# Mixer-Analog-OPA1644-Rev-E_TH_remaining0.net
KiCad netlist of a schematic drawn in EAGLE
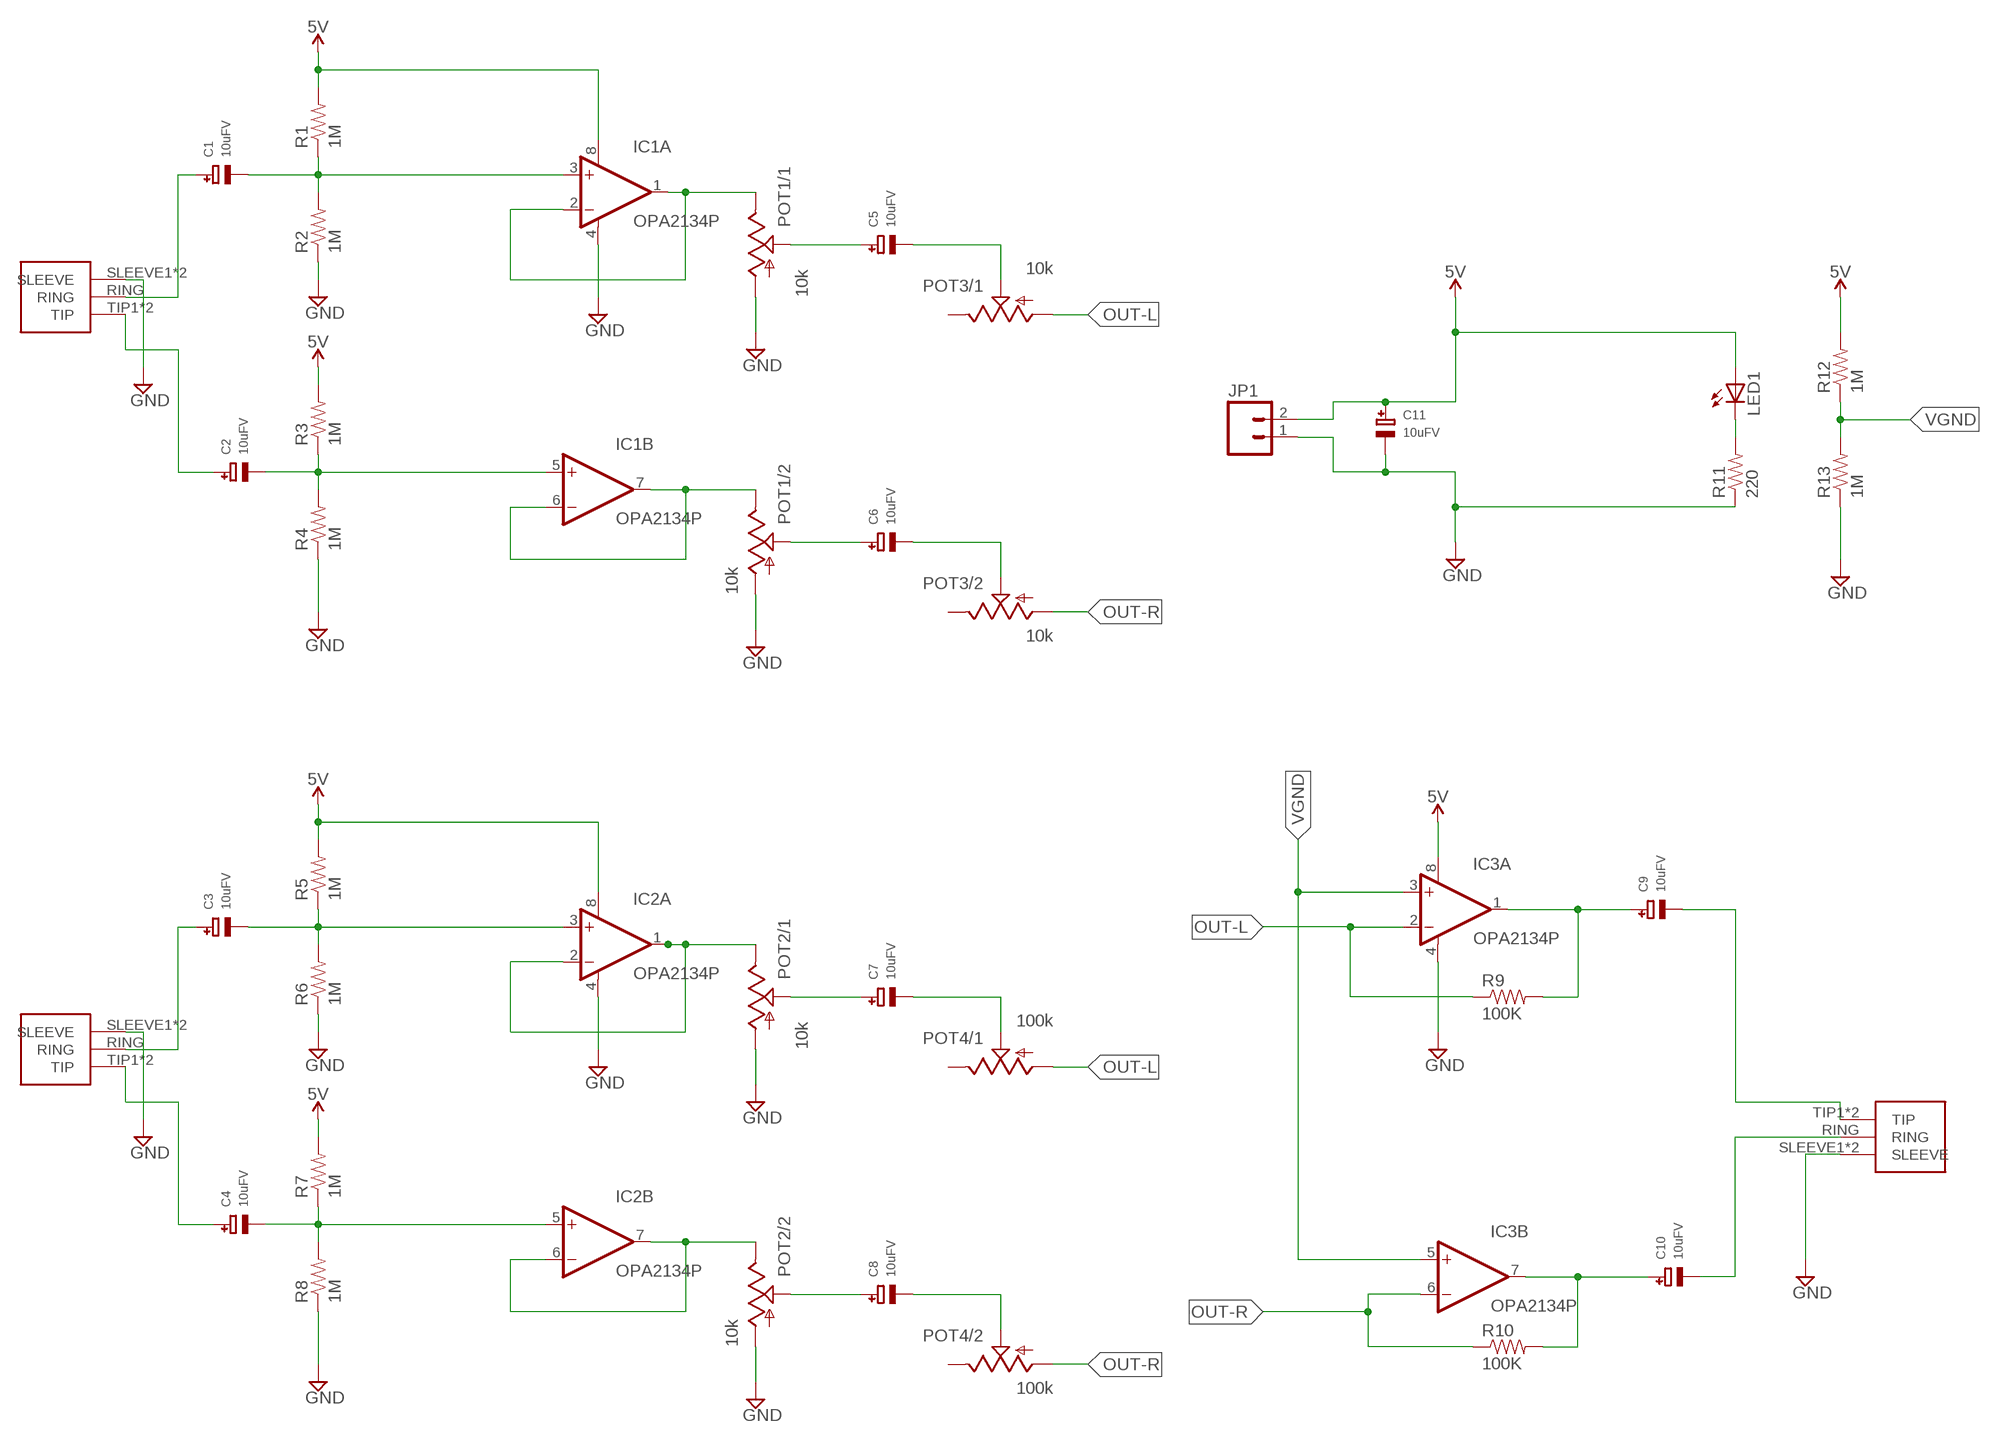
[diagram p0: schematic, sheet 1]

(export (version "E")
  (design (tool "Eeschema 10.0.6"))
  (components
    (comp (ref "C1")
      (value "10uFV")
      (footprint "eagle-import:CELEC_3.5MM_8MM")
      (libsource (lib "eagle-import") (part "CAP_ELECTROLYTICPTH_3.5MMGRID_8MMDIA"))
    )
    (comp (ref "C2")
      (value "10uFV")
      (footprint "eagle-import:CELEC_3.5MM_8MM")
      (libsource (lib "eagle-import") (part "CAP_ELECTROLYTICPTH_3.5MMGRID_8MMDIA"))
    )
    (comp (ref "C3")
      (value "10uFV")
      (footprint "eagle-import:CELEC_3.5MM_8MM")
      (libsource (lib "eagle-import") (part "CAP_ELECTROLYTICPTH_3.5MMGRID_8MMDIA"))
    )
    (comp (ref "C4")
      (value "10uFV")
      (footprint "eagle-import:CELEC_3.5MM_8MM")
      (libsource (lib "eagle-import") (part "CAP_ELECTROLYTICPTH_3.5MMGRID_8MMDIA"))
    )
    (comp (ref "C5")
      (value "10uFV")
      (footprint "eagle-import:CELEC_3.5MM_8MM")
      (libsource (lib "eagle-import") (part "CAP_ELECTROLYTICPTH_3.5MMGRID_8MMDIA"))
    )
    (comp (ref "C6")
      (value "10uFV")
      (footprint "eagle-import:CELEC_3.5MM_8MM")
      (libsource (lib "eagle-import") (part "CAP_ELECTROLYTICPTH_3.5MMGRID_8MMDIA"))
    )
    (comp (ref "C7")
      (value "10uFV")
      (footprint "eagle-import:CELEC_3.5MM_8MM")
      (libsource (lib "eagle-import") (part "CAP_ELECTROLYTICPTH_3.5MMGRID_8MMDIA"))
    )
    (comp (ref "C8")
      (value "10uFV")
      (footprint "eagle-import:CELEC_3.5MM_8MM")
      (libsource (lib "eagle-import") (part "CAP_ELECTROLYTICPTH_3.5MMGRID_8MMDIA"))
    )
    (comp (ref "C9")
      (value "10uFV")
      (footprint "eagle-import:CELEC_3.5MM_8MM")
      (libsource (lib "eagle-import") (part "CAP_ELECTROLYTICPTH_3.5MMGRID_8MMDIA"))
    )
    (comp (ref "C10")
      (value "10uFV")
      (footprint "eagle-import:CELEC_3.5MM_8MM")
      (libsource (lib "eagle-import") (part "CAP_ELECTROLYTICPTH_3.5MMGRID_8MMDIA"))
    )
    (comp (ref "C11")
      (value "10uFV")
      (footprint "eagle-import:CELEC_3.5MM_8MM")
      (libsource (lib "eagle-import") (part "CAP_ELECTROLYTICPTH_3.5MMGRID_8MMDIA"))
    )
    (comp (ref "IC1")
      (value "OPA2134P")
      (footprint "eagle-import:DIL08")
      (fields (field (name "MF") "TEXAS INSTRUMENTS") (field (name "MPN") "OPA2134PA"))
      (libsource (lib "eagle-import") (part "OPA2134P"))
    )
    (comp (ref "IC2")
      (value "OPA2134P")
      (footprint "eagle-import:DIL08")
      (fields (field (name "MF") "TEXAS INSTRUMENTS") (field (name "MPN") "OPA2134PA"))
      (libsource (lib "eagle-import") (part "OPA2134P"))
    )
    (comp (ref "IC3")
      (value "OPA2134P")
      (footprint "eagle-import:DIL08")
      (fields (field (name "MF") "TEXAS INSTRUMENTS") (field (name "MPN") "OPA2134PA"))
      (libsource (lib "eagle-import") (part "OPA2134P"))
    )
    (comp (ref "J1")
      (value "1/8\"-F-STEREO-PCB")
      (footprint "eagle-import:1_8_-F-STEREO-PCB")
      (libsource (lib "eagle-import") (part "1/8{dblquote}-F-STEREO-PCB"))
    )
    (comp (ref "J2")
      (value "1/8\"-F-STEREO-PCB")
      (footprint "eagle-import:1_8_-F-STEREO-PCB")
      (libsource (lib "eagle-import") (part "1/8{dblquote}-F-STEREO-PCB"))
    )
    (comp (ref "J3")
      (value "1/8\"-F-STEREO-PCB")
      (footprint "eagle-import:1_8_-F-STEREO-PCB")
      (libsource (lib "eagle-import") (part "1/8{dblquote}-F-STEREO-PCB"))
    )
    (comp (ref "JP1")
      (value "M02LOCK")
      (footprint "eagle-import:1X02_LOCK")
      (libsource (lib "eagle-import") (part "M02LOCK"))
    )
    (comp (ref "LED1")
      (value "LED3MM")
      (footprint "eagle-import:LED3MM")
      (libsource (lib "eagle-import") (part "LED3MM"))
    )
    (comp (ref "POT1")
      (value "10k")
      (footprint "eagle-import:PTV112")
      (fields
        (field (name "MF") "STMicroelectronics")
        (field (name "MP") "PTV112")
        (field (name "SPICEPREFIX") "J")
      )
      (libsource (lib "eagle-import") (part "POT-DUAL-PTV112-4420"))
    )
    (comp (ref "POT2")
      (value "10k")
      (footprint "eagle-import:PTV112")
      (fields
        (field (name "MF") "STMicroelectronics")
        (field (name "MP") "PTV112")
        (field (name "SPICEPREFIX") "J")
      )
      (libsource (lib "eagle-import") (part "POT-DUAL-PTV112-4420"))
    )
    (comp (ref "POT3")
      (value "10k")
      (footprint "eagle-import:PTV112")
      (fields
        (field (name "MF") "STMicroelectronics")
        (field (name "MP") "PTV112")
        (field (name "SPICEPREFIX") "J")
      )
      (libsource (lib "eagle-import") (part "POT-DUAL-PTV112-4420"))
    )
    (comp (ref "POT4")
      (value "100k")
      (footprint "eagle-import:PTV112")
      (fields
        (field (name "MF") "STMicroelectronics")
        (field (name "MP") "PTV112")
        (field (name "SPICEPREFIX") "J")
      )
      (libsource (lib "eagle-import") (part "POT-DUAL-PTV112-4420"))
    )
    (comp (ref "R1")
      (value "1M")
      (footprint "eagle-import:AXIAL-0.3EZ")
      (fields (field (name "SPICEPREFIX") "R"))
      (libsource (lib "eagle-import") (part "RESISTOREZ"))
    )
    (comp (ref "R2")
      (value "1M")
      (footprint "eagle-import:AXIAL-0.3")
      (fields (field (name "SPICEPREFIX") "R"))
      (libsource (lib "eagle-import") (part "RESISTORAXIAL-0.3"))
    )
    (comp (ref "R3")
      (value "1M")
      (footprint "eagle-import:AXIAL-0.3EZ")
      (fields (field (name "SPICEPREFIX") "R"))
      (libsource (lib "eagle-import") (part "RESISTOREZ"))
    )
    (comp (ref "R4")
      (value "1M")
      (footprint "eagle-import:AXIAL-0.3EZ")
      (fields (field (name "SPICEPREFIX") "R"))
      (libsource (lib "eagle-import") (part "RESISTOREZ"))
    )
    (comp (ref "R5")
      (value "1M")
      (footprint "eagle-import:AXIAL-0.3EZ")
      (fields (field (name "SPICEPREFIX") "R"))
      (libsource (lib "eagle-import") (part "RESISTOREZ"))
    )
    (comp (ref "R6")
      (value "1M")
      (footprint "eagle-import:AXIAL-0.3EZ")
      (fields (field (name "SPICEPREFIX") "R"))
      (libsource (lib "eagle-import") (part "RESISTOREZ"))
    )
    (comp (ref "R7")
      (value "1M")
      (footprint "eagle-import:AXIAL-0.3EZ")
      (fields (field (name "SPICEPREFIX") "R"))
      (libsource (lib "eagle-import") (part "RESISTOREZ"))
    )
    (comp (ref "R8")
      (value "1M")
      (footprint "eagle-import:AXIAL-0.3EZ")
      (fields (field (name "SPICEPREFIX") "R"))
      (libsource (lib "eagle-import") (part "RESISTOREZ"))
    )
    (comp (ref "R9")
      (value "100K")
      (footprint "eagle-import:AXIAL-0.3EZ")
      (fields (field (name "SPICEPREFIX") "R"))
      (libsource (lib "eagle-import") (part "RESISTOREZ"))
    )
    (comp (ref "R10")
      (value "100K")
      (footprint "eagle-import:AXIAL-0.3EZ")
      (fields (field (name "SPICEPREFIX") "R"))
      (libsource (lib "eagle-import") (part "RESISTOREZ"))
    )
    (comp (ref "R11")
      (value "220")
      (footprint "eagle-import:AXIAL-0.3EZ")
      (libsource (lib "eagle-import") (part "RESISTOREZ"))
    )
    (comp (ref "R12")
      (value "1M")
      (footprint "eagle-import:AXIAL-0.3EZ")
      (libsource (lib "eagle-import") (part "RESISTOREZ"))
    )
    (comp (ref "R13")
      (value "1M")
      (footprint "eagle-import:AXIAL-0.3EZ")
      (libsource (lib "eagle-import") (part "RESISTOREZ"))
    )
  )
  (nets
    (net (code "1") (name "5V") (class "Default")
      (node (ref "C11") (pin "+") (pinfunction "+_+") (pintype "passive"))
      (node (ref "IC1") (pin "8") (pinfunction "V+_8") (pintype "power_in"))
      (node (ref "IC2") (pin "8") (pinfunction "V+_8") (pintype "power_in"))
      (node (ref "IC3") (pin "8") (pinfunction "V+_8") (pintype "power_in"))
      (node (ref "JP1") (pin "2") (pinfunction "2_2") (pintype "passive"))
      (node (ref "LED1") (pin "A") (pinfunction "A_A") (pintype "passive"))
      (node (ref "R1") (pin "P$2") (pinfunction "2_P$2") (pintype "passive"))
      (node (ref "R12") (pin "P$2") (pinfunction "2_P$2") (pintype "passive"))
      (node (ref "R3") (pin "P$2") (pinfunction "2_P$2") (pintype "passive"))
      (node (ref "R5") (pin "P$2") (pinfunction "2_P$2") (pintype "passive"))
      (node (ref "R7") (pin "P$2") (pinfunction "2_P$2") (pintype "passive"))
    )
    (net (code "2") (name "GND") (class "Default")
      (node (ref "C11") (pin "-") (pinfunction "-_-") (pintype "passive"))
      (node (ref "IC1") (pin "4") (pinfunction "V-_4") (pintype "power_in"))
      (node (ref "IC2") (pin "4") (pinfunction "V-_4") (pintype "power_in"))
      (node (ref "IC3") (pin "4") (pinfunction "V-_4") (pintype "power_in"))
      (node (ref "J1") (pin "SLEEVE1") (pinfunction "SLEEVE_SLEEVE1") (pintype "bidirectional"))
      (node (ref "J1") (pin "SLEEVE2") (pinfunction "SLEEVE_SLEEVE2") (pintype "bidirectional"))
      (node (ref "J2") (pin "SLEEVE1") (pinfunction "SLEEVE_SLEEVE1") (pintype "bidirectional"))
      (node (ref "J2") (pin "SLEEVE2") (pinfunction "SLEEVE_SLEEVE2") (pintype "bidirectional"))
      (node (ref "J3") (pin "SLEEVE1") (pinfunction "SLEEVE_SLEEVE1") (pintype "bidirectional"))
      (node (ref "J3") (pin "SLEEVE2") (pinfunction "SLEEVE_SLEEVE2") (pintype "bidirectional"))
      (node (ref "JP1") (pin "1") (pinfunction "1_1") (pintype "passive"))
      (node (ref "POT1") (pin "1.1") (pinfunction "A_1.1") (pintype "passive"))
      (node (ref "POT1") (pin "2.1") (pinfunction "A_2.1") (pintype "passive"))
      (node (ref "POT2") (pin "1.1") (pinfunction "A_1.1") (pintype "passive"))
      (node (ref "POT2") (pin "2.1") (pinfunction "A_2.1") (pintype "passive"))
      (node (ref "R11") (pin "P$1") (pinfunction "1_P$1") (pintype "passive"))
      (node (ref "R13") (pin "P$1") (pinfunction "1_P$1") (pintype "passive"))
      (node (ref "R2") (pin "P$1") (pinfunction "1_P$1") (pintype "passive"))
      (node (ref "R4") (pin "P$1") (pinfunction "1_P$1") (pintype "passive"))
      (node (ref "R6") (pin "P$1") (pinfunction "1_P$1") (pintype "passive"))
      (node (ref "R8") (pin "P$1") (pinfunction "1_P$1") (pintype "passive"))
    )
    (net (code "3") (name "Net-(C1-Pad+)") (class "Default")
      (node (ref "C1") (pin "+") (pinfunction "+_+") (pintype "passive"))
      (node (ref "J1") (pin "RING") (pinfunction "RING_RING") (pintype "bidirectional"))
    )
    (net (code "4") (name "Net-(C2-Pad+)") (class "Default")
      (node (ref "C2") (pin "+") (pinfunction "+_+") (pintype "passive"))
      (node (ref "J1") (pin "TIP1") (pinfunction "TIP_TIP1") (pintype "bidirectional"))
      (node (ref "J1") (pin "TIP2") (pinfunction "TIP_TIP2") (pintype "bidirectional"))
    )
    (net (code "5") (name "Net-(C3-Pad+)") (class "Default")
      (node (ref "C3") (pin "+") (pinfunction "+_+") (pintype "passive"))
      (node (ref "J2") (pin "RING") (pinfunction "RING_RING") (pintype "bidirectional"))
    )
    (net (code "6") (name "Net-(C4-Pad+)") (class "Default")
      (node (ref "C4") (pin "+") (pinfunction "+_+") (pintype "passive"))
      (node (ref "J2") (pin "TIP1") (pinfunction "TIP_TIP1") (pintype "bidirectional"))
      (node (ref "J2") (pin "TIP2") (pinfunction "TIP_TIP2") (pintype "bidirectional"))
    )
    (net (code "7") (name "Net-(C9-Pad-)") (class "Default")
      (node (ref "C9") (pin "-") (pinfunction "-_-") (pintype "passive"))
      (node (ref "J3") (pin "TIP1") (pinfunction "TIP_TIP1") (pintype "bidirectional"))
      (node (ref "J3") (pin "TIP2") (pinfunction "TIP_TIP2") (pintype "bidirectional"))
    )
    (net (code "8") (name "Net-(C10-Pad-)") (class "Default")
      (node (ref "C10") (pin "-") (pinfunction "-_-") (pintype "passive"))
      (node (ref "J3") (pin "RING") (pinfunction "RING_RING") (pintype "bidirectional"))
    )
    (net (code "9") (name "Net-(IC1A-+IN)") (class "Default")
      (node (ref "C1") (pin "-") (pinfunction "-_-") (pintype "passive"))
      (node (ref "IC1") (pin "3") (pinfunction "+IN_3") (pintype "input"))
      (node (ref "R1") (pin "P$1") (pinfunction "1_P$1") (pintype "passive"))
      (node (ref "R2") (pin "P$2") (pinfunction "2_P$2") (pintype "passive"))
    )
    (net (code "10") (name "Net-(IC1A--IN)") (class "Default")
      (node (ref "IC1") (pin "1") (pinfunction "OUT_1") (pintype "output"))
      (node (ref "IC1") (pin "2") (pinfunction "-IN_2") (pintype "input"))
      (node (ref "POT1") (pin "1.3") (pinfunction "E_1.3") (pintype "passive"))
    )
    (net (code "11") (name "Net-(IC1B-+IN)") (class "Default")
      (node (ref "C2") (pin "-") (pinfunction "-_-") (pintype "passive"))
      (node (ref "IC1") (pin "5") (pinfunction "+IN_5") (pintype "input"))
      (node (ref "R3") (pin "P$1") (pinfunction "1_P$1") (pintype "passive"))
      (node (ref "R4") (pin "P$2") (pinfunction "2_P$2") (pintype "passive"))
    )
    (net (code "12") (name "Net-(IC1B--IN)") (class "Default")
      (node (ref "IC1") (pin "6") (pinfunction "-IN_6") (pintype "input"))
      (node (ref "IC1") (pin "7") (pinfunction "OUT_7") (pintype "output"))
      (node (ref "POT1") (pin "2.3") (pinfunction "E_2.3") (pintype "passive"))
    )
    (net (code "13") (name "Net-(IC2A-+IN)") (class "Default")
      (node (ref "C3") (pin "-") (pinfunction "-_-") (pintype "passive"))
      (node (ref "IC2") (pin "3") (pinfunction "+IN_3") (pintype "input"))
      (node (ref "R5") (pin "P$1") (pinfunction "1_P$1") (pintype "passive"))
      (node (ref "R6") (pin "P$2") (pinfunction "2_P$2") (pintype "passive"))
    )
    (net (code "14") (name "Net-(IC2A--IN)") (class "Default")
      (node (ref "IC2") (pin "1") (pinfunction "OUT_1") (pintype "output"))
      (node (ref "IC2") (pin "2") (pinfunction "-IN_2") (pintype "input"))
      (node (ref "POT2") (pin "1.3") (pinfunction "E_1.3") (pintype "passive"))
    )
    (net (code "15") (name "Net-(IC2B-+IN)") (class "Default")
      (node (ref "C4") (pin "-") (pinfunction "-_-") (pintype "passive"))
      (node (ref "IC2") (pin "5") (pinfunction "+IN_5") (pintype "input"))
      (node (ref "R7") (pin "P$1") (pinfunction "1_P$1") (pintype "passive"))
      (node (ref "R8") (pin "P$2") (pinfunction "2_P$2") (pintype "passive"))
    )
    (net (code "16") (name "Net-(IC2B--IN)") (class "Default")
      (node (ref "IC2") (pin "6") (pinfunction "-IN_6") (pintype "input"))
      (node (ref "IC2") (pin "7") (pinfunction "OUT_7") (pintype "output"))
      (node (ref "POT2") (pin "2.3") (pinfunction "E_2.3") (pintype "passive"))
    )
    (net (code "17") (name "Net-(IC3A-OUT)") (class "Default")
      (node (ref "C9") (pin "+") (pinfunction "+_+") (pintype "passive"))
      (node (ref "IC3") (pin "1") (pinfunction "OUT_1") (pintype "output"))
      (node (ref "R9") (pin "P$2") (pinfunction "2_P$2") (pintype "passive"))
    )
    (net (code "18") (name "Net-(IC3B-OUT)") (class "Default")
      (node (ref "C10") (pin "+") (pinfunction "+_+") (pintype "passive"))
      (node (ref "IC3") (pin "7") (pinfunction "OUT_7") (pintype "output"))
      (node (ref "R10") (pin "P$2") (pinfunction "2_P$2") (pintype "passive"))
    )
    (net (code "19") (name "Net-(LED1-C)") (class "Default")
      (node (ref "LED1") (pin "K") (pinfunction "C_K") (pintype "passive"))
      (node (ref "R11") (pin "P$2") (pinfunction "2_P$2") (pintype "passive"))
    )
    (net (code "20") (name "Net-(POT1A-S)") (class "Default")
      (node (ref "C5") (pin "+") (pinfunction "+_+") (pintype "passive"))
      (node (ref "POT1") (pin "1.2") (pinfunction "S_1.2") (pintype "passive"))
    )
    (net (code "21") (name "Net-(POT1B-S)") (class "Default")
      (node (ref "C6") (pin "+") (pinfunction "+_+") (pintype "passive"))
      (node (ref "POT1") (pin "2.2") (pinfunction "S_2.2") (pintype "passive"))
    )
    (net (code "22") (name "Net-(POT2A-S)") (class "Default")
      (node (ref "C7") (pin "+") (pinfunction "+_+") (pintype "passive"))
      (node (ref "POT2") (pin "1.2") (pinfunction "S_1.2") (pintype "passive"))
    )
    (net (code "23") (name "Net-(POT2B-S)") (class "Default")
      (node (ref "C8") (pin "+") (pinfunction "+_+") (pintype "passive"))
      (node (ref "POT2") (pin "2.2") (pinfunction "S_2.2") (pintype "passive"))
    )
    (net (code "24") (name "Net-(POT3A-S)") (class "Default")
      (node (ref "C5") (pin "-") (pinfunction "-_-") (pintype "passive"))
      (node (ref "POT3") (pin "1.2") (pinfunction "S_1.2") (pintype "passive"))
    )
    (net (code "25") (name "Net-(POT3B-S)") (class "Default")
      (node (ref "C6") (pin "-") (pinfunction "-_-") (pintype "passive"))
      (node (ref "POT3") (pin "2.2") (pinfunction "S_2.2") (pintype "passive"))
    )
    (net (code "26") (name "Net-(POT4A-S)") (class "Default")
      (node (ref "C7") (pin "-") (pinfunction "-_-") (pintype "passive"))
      (node (ref "POT4") (pin "1.2") (pinfunction "S_1.2") (pintype "passive"))
    )
    (net (code "27") (name "Net-(POT4B-S)") (class "Default")
      (node (ref "C8") (pin "-") (pinfunction "-_-") (pintype "passive"))
      (node (ref "POT4") (pin "2.2") (pinfunction "S_2.2") (pintype "passive"))
    )
    (net (code "28") (name "OUT-L") (class "Default")
      (node (ref "IC3") (pin "2") (pinfunction "-IN_2") (pintype "input"))
      (node (ref "POT3") (pin "1.1") (pinfunction "A_1.1") (pintype "passive"))
      (node (ref "POT4") (pin "1.1") (pinfunction "A_1.1") (pintype "passive"))
      (node (ref "R9") (pin "P$1") (pinfunction "1_P$1") (pintype "passive"))
    )
    (net (code "29") (name "OUT-R") (class "Default")
      (node (ref "IC3") (pin "6") (pinfunction "-IN_6") (pintype "input"))
      (node (ref "POT3") (pin "2.1") (pinfunction "A_2.1") (pintype "passive"))
      (node (ref "POT4") (pin "2.1") (pinfunction "A_2.1") (pintype "passive"))
      (node (ref "R10") (pin "P$1") (pinfunction "1_P$1") (pintype "passive"))
    )
    (net (code "30") (name "VGND") (class "Default")
      (node (ref "IC3") (pin "3") (pinfunction "+IN_3") (pintype "input"))
      (node (ref "IC3") (pin "5") (pinfunction "+IN_5") (pintype "input"))
      (node (ref "R12") (pin "P$1") (pinfunction "1_P$1") (pintype "passive"))
      (node (ref "R13") (pin "P$2") (pinfunction "2_P$2") (pintype "passive"))
    )
    (net (code "31") (name "unconnected-(POT3A-E-Pad1.3)") (class "Default")
      (node (ref "POT3") (pin "1.3") (pinfunction "E_1.3") (pintype "passive"))
    )
    (net (code "32") (name "unconnected-(POT3B-E-Pad2.3)") (class "Default")
      (node (ref "POT3") (pin "2.3") (pinfunction "E_2.3") (pintype "passive"))
    )
    (net (code "33") (name "unconnected-(POT4A-E-Pad1.3)") (class "Default")
      (node (ref "POT4") (pin "1.3") (pinfunction "E_1.3") (pintype "passive"))
    )
    (net (code "34") (name "unconnected-(POT4B-E-Pad2.3)") (class "Default")
      (node (ref "POT4") (pin "2.3") (pinfunction "E_2.3") (pintype "passive"))
    )
  )
)
